# Openbook_Schematics.net
KiCad netlist of a schematic drawn in EAGLE
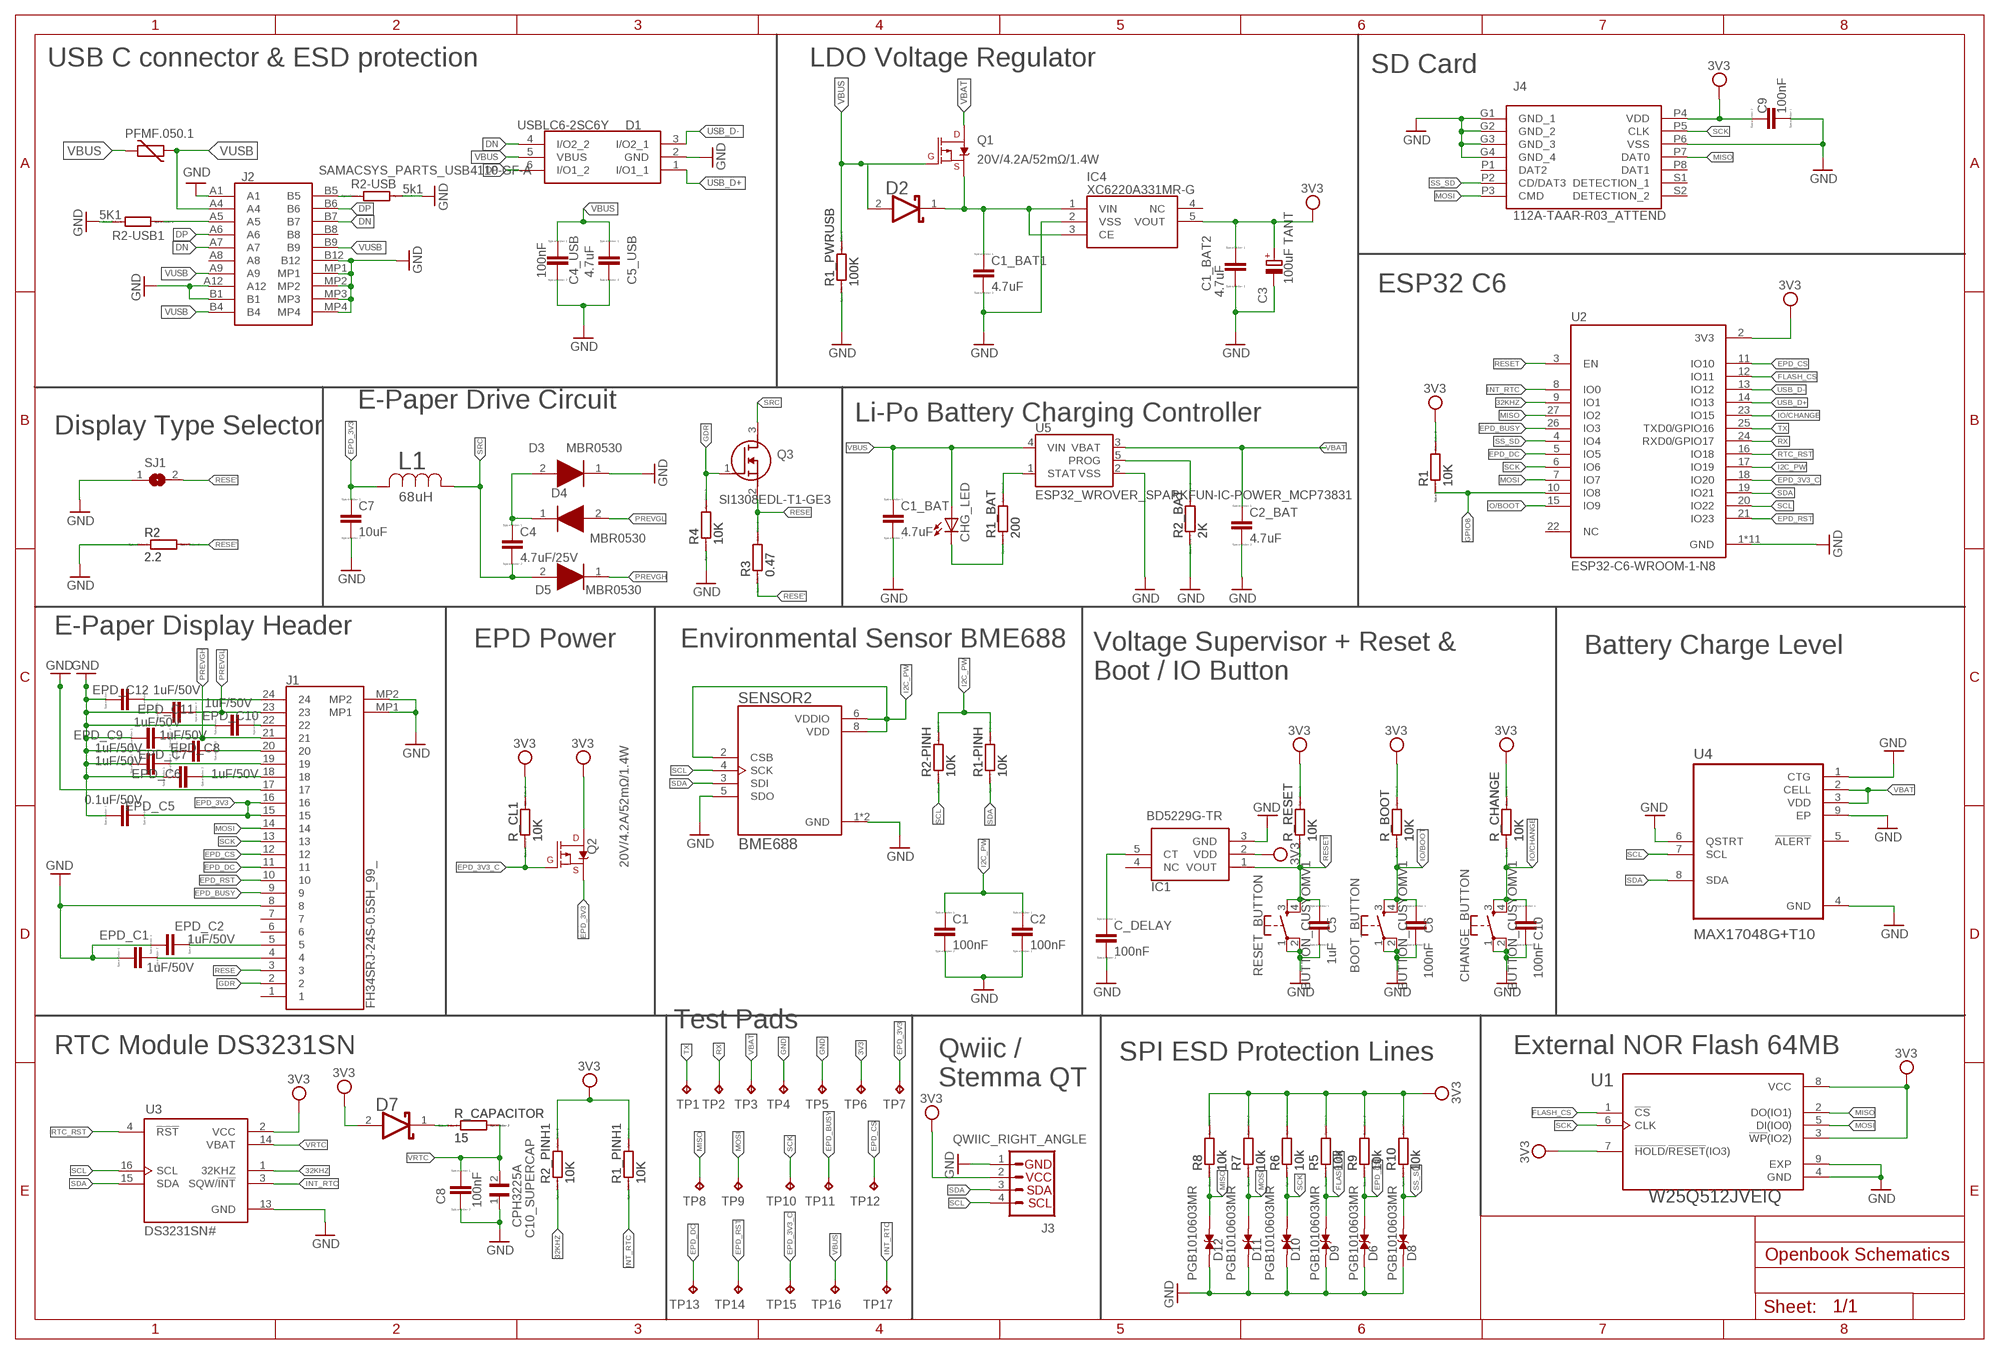
[diagram p0: schematic, sheet 1]

(export (version "E")
  (design (tool "Eeschema 10.0.6"))
  (components
    (comp (ref "BOOT_BUTTON")
      (value "BUTTON_CUSYOMV1")
      (footprint "eagle-import:MYBUTTON")
      (libsource (lib "eagle-import") (part "BUTTON_CUSYOMV1"))
    )
    (comp (ref "C1")
      (value "100nF")
      (footprint "eagle-import:EAGLE-LTSPICE_C0402")
      (libsource (lib "eagle-import") (part "EAGLE-LTSPICE_CC0402"))
    )
    (comp (ref "C1_BAT")
      (value "4.7uF")
      (footprint "eagle-import:EAGLE-LTSPICE_C0402")
      (libsource (lib "eagle-import") (part "EAGLE-LTSPICE_CC0402"))
    )
    (comp (ref "C1_BAT1")
      (value "4.7uF")
      (footprint "eagle-import:ESP32_WROVER_EAGLE-LTSPICE_C0402")
      (libsource (lib "eagle-import") (part "ESP32_WROVER_EAGLE-LTSPICE_CC0402"))
    )
    (comp (ref "C1_BAT2")
      (value "4.7uF")
      (footprint "eagle-import:EAGLE-LTSPICE_C0402")
      (libsource (lib "eagle-import") (part "EAGLE-LTSPICE_CC0402"))
    )
    (comp (ref "C2")
      (value "100nF")
      (footprint "eagle-import:EAGLE-LTSPICE_C0402")
      (libsource (lib "eagle-import") (part "EAGLE-LTSPICE_CC0402"))
    )
    (comp (ref "C2_BAT")
      (value "4.7uF")
      (footprint "eagle-import:EAGLE-LTSPICE_C0402")
      (libsource (lib "eagle-import") (part "EAGLE-LTSPICE_CC0402"))
    )
    (comp (ref "C3")
      (value "100uF TANT")
      (footprint "eagle-import:RCL_CT3528")
      (libsource (lib "eagle-import") (part "RCL_CPOL-EUCT3528"))
    )
    (comp (ref "C4")
      (value "4.7uF/25V")
      (footprint "eagle-import:EAGLE-LTSPICE_C0402")
      (libsource (lib "eagle-import") (part "EAGLE-LTSPICE_CC0402"))
    )
    (comp (ref "C4_USB")
      (value "100nF")
      (footprint "eagle-import:EAGLE-LTSPICE_C0402")
      (libsource (lib "eagle-import") (part "EAGLE-LTSPICE_CC0402"))
    )
    (comp (ref "C5")
      (value "1uF")
      (footprint "eagle-import:EAGLE-LTSPICE_C0402")
      (libsource (lib "eagle-import") (part "EAGLE-LTSPICE_CC0402"))
    )
    (comp (ref "C5_USB")
      (value "4.7uF")
      (footprint "eagle-import:EAGLE-LTSPICE_C0402")
      (libsource (lib "eagle-import") (part "EAGLE-LTSPICE_CC0402"))
    )
    (comp (ref "C6")
      (value "100nF")
      (footprint "eagle-import:EAGLE-LTSPICE_C0402")
      (libsource (lib "eagle-import") (part "EAGLE-LTSPICE_CC0402"))
    )
    (comp (ref "C7")
      (value "10uF")
      (footprint "eagle-import:EAGLE-LTSPICE_C0402")
      (libsource (lib "eagle-import") (part "EAGLE-LTSPICE_CC0402"))
    )
    (comp (ref "C8")
      (value "100nF")
      (footprint "eagle-import:EAGLE-LTSPICE_C0402")
      (libsource (lib "eagle-import") (part "EAGLE-LTSPICE_CC0402"))
    )
    (comp (ref "C9")
      (value "100nF")
      (footprint "eagle-import:EAGLE-LTSPICE_C0402")
      (libsource (lib "eagle-import") (part "EAGLE-LTSPICE_CC0402"))
    )
    (comp (ref "C10")
      (value "100nF")
      (footprint "eagle-import:EAGLE-LTSPICE_C0402")
      (libsource (lib "eagle-import") (part "EAGLE-LTSPICE_CC0402"))
    )
    (comp (ref "C10_SUPERCAP")
      (value "CPH3225A")
      (footprint "eagle-import:CAPCP3225X100N")
      (fields (field (name "MF") "Seiko Instruments"))
      (libsource (lib "eagle-import") (part "CPH3225A"))
    )
    (comp (ref "CHANGE_BUTTON")
      (value "BUTTON_CUSYOMV1")
      (footprint "eagle-import:MYBUTTON")
      (libsource (lib "eagle-import") (part "BUTTON_CUSYOMV1"))
    )
    (comp (ref "CHG_LED")
      (value "ADAFRUIT_LEDCHIP-LED0603")
      (footprint "eagle-import:ADAFRUIT_CHIP-LED0603")
      (libsource (lib "eagle-import") (part "ADAFRUIT_LEDCHIP-LED0603"))
    )
    (comp (ref "C_DELAY")
      (value "100nF")
      (footprint "eagle-import:EAGLE-LTSPICE_C0402")
      (libsource (lib "eagle-import") (part "EAGLE-LTSPICE_CC0402"))
    )
    (comp (ref "D1")
      (value "USBLC6-2SC6Y")
      (footprint "eagle-import:SOT95P280X145-6N")
      (fields (field (name "MF") "STMicroelectronics"))
      (libsource (lib "eagle-import") (part "USBLC6-2SC6Y"))
    )
    (comp (ref "D2")
      (value "ESP32_WROVER_AVX---SD0805S020S1R0_AVX_SD0805S020S1R0_0_0AVX_SD0805S020S1R0_0_0")
      (footprint "eagle-import:ESP32_WROVER_AVX---SD0805S020S1R0_AVX_SD0805S020S1R0_0")
      (fields
        (field (name "DIGIKEY_PART_NUMBER") "478-7800-1-ND")
        (field (name "MF") "AVX")
        (field (name "MOUSER_PART_NUMBER") "581-SD0805S020S1R0")
      )
      (libsource (lib "eagle-import") (part "ESP32_WROVER_AVX---SD0805S020S1R0_AVX_SD0805S020S1R0_0_0AVX_SD0805S020S1R0_0_0"))
    )
    (comp (ref "D3")
      (value "MBR0530")
      (footprint "eagle-import:SOD3716X135N")
      (fields (field (name "MF") "ON Semiconductor"))
      (libsource (lib "eagle-import") (part "MBR0530"))
    )
    (comp (ref "D4")
      (value "MBR0530")
      (footprint "eagle-import:SOD3716X135N")
      (fields (field (name "MF") "ON Semiconductor"))
      (libsource (lib "eagle-import") (part "MBR0530"))
    )
    (comp (ref "D5")
      (value "MBR0530")
      (footprint "eagle-import:SOD3716X135N")
      (fields (field (name "MF") "ON Semiconductor"))
      (libsource (lib "eagle-import") (part "MBR0530"))
    )
    (comp (ref "D6")
      (value "PGB1010603MR")
      (footprint "eagle-import:DIOC1608X36N")
      (fields (field (name "MF") "Littelfuse Inc."))
      (libsource (lib "eagle-import") (part "PGB1010603MR"))
    )
    (comp (ref "D7")
      (value "ESP32_WROVER_AVX---SD0805S020S1R0_AVX_SD0805S020S1R0_0_0AVX_SD0805S020S1R0_0_0")
      (footprint "eagle-import:ESP32_WROVER_AVX---SD0805S020S1R0_AVX_SD0805S020S1R0_0")
      (fields
        (field (name "DIGIKEY_PART_NUMBER") "478-7800-1-ND")
        (field (name "MF") "AVX")
        (field (name "MOUSER_PART_NUMBER") "581-SD0805S020S1R0")
      )
      (libsource (lib "eagle-import") (part "ESP32_WROVER_AVX---SD0805S020S1R0_AVX_SD0805S020S1R0_0_0AVX_SD0805S020S1R0_0_0"))
    )
    (comp (ref "D8")
      (value "PGB1010603MR")
      (footprint "eagle-import:DIOC1608X36N")
      (fields (field (name "MF") "Littelfuse Inc."))
      (libsource (lib "eagle-import") (part "PGB1010603MR"))
    )
    (comp (ref "D9")
      (value "PGB1010603MR")
      (footprint "eagle-import:DIOC1608X36N")
      (fields (field (name "MF") "Littelfuse Inc."))
      (libsource (lib "eagle-import") (part "PGB1010603MR"))
    )
    (comp (ref "D10")
      (value "PGB1010603MR")
      (footprint "eagle-import:DIOC1608X36N")
      (fields (field (name "MF") "Littelfuse Inc."))
      (libsource (lib "eagle-import") (part "PGB1010603MR"))
    )
    (comp (ref "D11")
      (value "PGB1010603MR")
      (footprint "eagle-import:DIOC1608X36N")
      (fields (field (name "MF") "Littelfuse Inc."))
      (libsource (lib "eagle-import") (part "PGB1010603MR"))
    )
    (comp (ref "D12")
      (value "PGB1010603MR")
      (footprint "eagle-import:DIOC1608X36N")
      (fields (field (name "MF") "Littelfuse Inc."))
      (libsource (lib "eagle-import") (part "PGB1010603MR"))
    )
    (comp (ref "EPD_C1")
      (value "1uF/50V")
      (footprint "eagle-import:EAGLE-LTSPICE_C0402")
      (libsource (lib "eagle-import") (part "EAGLE-LTSPICE_CC0402"))
    )
    (comp (ref "EPD_C2")
      (value "1uF/50V")
      (footprint "eagle-import:EAGLE-LTSPICE_C0402")
      (libsource (lib "eagle-import") (part "EAGLE-LTSPICE_CC0402"))
    )
    (comp (ref "EPD_C5")
      (value "0.1uF/50V")
      (footprint "eagle-import:EAGLE-LTSPICE_C0402")
      (libsource (lib "eagle-import") (part "EAGLE-LTSPICE_CC0402"))
    )
    (comp (ref "EPD_C6")
      (value "1uF/50V")
      (footprint "eagle-import:EAGLE-LTSPICE_C0402")
      (libsource (lib "eagle-import") (part "EAGLE-LTSPICE_CC0402"))
    )
    (comp (ref "EPD_C7")
      (value "1uF/50V")
      (footprint "eagle-import:EAGLE-LTSPICE_C0402")
      (libsource (lib "eagle-import") (part "EAGLE-LTSPICE_CC0402"))
    )
    (comp (ref "EPD_C8")
      (value "1uF/50V")
      (footprint "eagle-import:EAGLE-LTSPICE_C0402")
      (libsource (lib "eagle-import") (part "EAGLE-LTSPICE_CC0402"))
    )
    (comp (ref "EPD_C9")
      (value "1uF/50V")
      (footprint "eagle-import:EAGLE-LTSPICE_C0402")
      (libsource (lib "eagle-import") (part "EAGLE-LTSPICE_CC0402"))
    )
    (comp (ref "EPD_C10")
      (value "1uF/50V")
      (footprint "eagle-import:EAGLE-LTSPICE_C0402")
      (libsource (lib "eagle-import") (part "EAGLE-LTSPICE_CC0402"))
    )
    (comp (ref "EPD_C11")
      (value "1uF/50V")
      (footprint "eagle-import:EAGLE-LTSPICE_C0402")
      (libsource (lib "eagle-import") (part "EAGLE-LTSPICE_CC0402"))
    )
    (comp (ref "EPD_C12")
      (value "1uF/50V")
      (footprint "eagle-import:EAGLE-LTSPICE_C0402")
      (libsource (lib "eagle-import") (part "EAGLE-LTSPICE_CC0402"))
    )
    (comp (ref "IC1")
      (value "BD5229G-TR")
      (footprint "eagle-import:SOT95P280X125-5N")
      (fields (field (name "MOUSER_PART_NUMBER") "755-BD5229G-TR"))
      (libsource (lib "eagle-import") (part "BD5229G-TR"))
    )
    (comp (ref "IC4")
      (value "XC6220A331MR-G")
      (footprint "eagle-import:SOT95P280X120-5N")
      (fields (field (name "MOUSER_PART_NUMBER") "865-XC6220A331MR-G"))
      (libsource (lib "eagle-import") (part "XC6220A331MR-G"))
    )
    (comp (ref "J1")
      (value "FH34SRJ-24S-0.5SH_99_")
      (footprint "eagle-import:FH34SRJ24S05SH99")
      (fields
        (field (name "MANUFACTURER_PART_NUMBER") "FH34SRJ-24S-0.5SH(99)")
        (field (name "MOUSER_PART_NUMBER") "798-FH34SRJ24S05SH99")
      )
      (libsource (lib "eagle-import") (part "FH34SRJ-24S-0.5SH_99_"))
    )
    (comp (ref "J2")
      (value "SAMACSYS_PARTS_USB4110-GF-A")
      (footprint "eagle-import:SAMACSYS_PARTS_USB4110GFA")
      (fields
        (field (name "MANUFACTURER_PART_NUMBER") "USB4110-GF-A")
        (field (name "MOUSER_PART_NUMBER") "640-USB4110-GF-A")
      )
      (libsource (lib "eagle-import") (part "SAMACSYS_PARTS_USB4110-GF-A"))
    )
    (comp (ref "J3")
      (value "QWIIC_RIGHT_ANGLE")
      (footprint "eagle-import:JST04_1MM_RA")
      (libsource (lib "eagle-import") (part "QWIIC_CONNECTORJS-1MM"))
    )
    (comp (ref "J4")
      (value "112A-TAAR-R03_ATTEND")
      (footprint "eagle-import:112ATAARR03ATTEND")
      (fields (field (name "MANUFACTURER_PART_NUMBER") "112A-TAAR-R03 ATTEND"))
      (libsource (lib "eagle-import") (part "112A-TAAR-R03_ATTEND"))
    )
    (comp (ref "L1")
      (value "68uH")
      (footprint "eagle-import:IND_4828-WE-TPC_WRE")
      (fields
        (field (name "MANUFACTURER_PART_NUMBER") "744043680")
        (field (name "COPYRIGHT") "Copyright (C) 2024 Ultra Librarian. All rights reserved.")
      )
      (libsource (lib "eagle-import") (part "744043680IND_4828-WE-TPC_WRE"))
    )
    (comp (ref "PFMF.050.1")
      (value "ESP32C6_VARISTORCN1812")
      (footprint "eagle-import:ESP32C6_VARISTOR_CT_CN1812")
      (libsource (lib "eagle-import") (part "ESP32C6_VARISTORCN1812"))
    )
    (comp (ref "Q1")
      (value "20V/4.2A/52mΩ/1.4W")
      (footprint "eagle-import:ESP32_WROVER_SPARKFUN-DISCRETESEMI_SOT23-3")
      (libsource (lib "eagle-import") (part "ESP32_WROVER_SPARKFUN-DISCRETESEMI_MOSFET_PCH-DMG2305UX-7"))
    )
    (comp (ref "Q2")
      (value "20V/4.2A/52mΩ/1.4W")
      (footprint "eagle-import:ESP32_WROVER_SPARKFUN-DISCRETESEMI_SOT23-3")
      (libsource (lib "eagle-import") (part "ESP32_WROVER_SPARKFUN-DISCRETESEMI_MOSFET_PCH-DMG2305UX-7"))
    )
    (comp (ref "Q3")
      (value "SI1308EDL-T1-GE3")
      (footprint "eagle-import:SOT65P210X110-3N")
      (fields (field (name "MF") "Vishay Siliconix"))
      (libsource (lib "eagle-import") (part "SI1308EDL-T1-GE3"))
    )
    (comp (ref "R1")
      (value "10K")
      (footprint "eagle-import:ESP32_WROVER_EAGLE-LTSPICE_R0402")
      (libsource (lib "eagle-import") (part "ESP32_WROVER_EAGLE-LTSPICE_RR0402"))
    )
    (comp (ref "R1-PINH")
      (value "10K")
      (footprint "eagle-import:ESP32_WROVER_EAGLE-LTSPICE_R0402")
      (libsource (lib "eagle-import") (part "ESP32_WROVER_EAGLE-LTSPICE_RR0402"))
    )
    (comp (ref "R1_BAT")
      (value "200")
      (footprint "eagle-import:ESP32_WROVER_EAGLE-LTSPICE_R0402")
      (libsource (lib "eagle-import") (part "ESP32_WROVER_EAGLE-LTSPICE_RR0402"))
    )
    (comp (ref "R1_PINH1")
      (value "10K")
      (footprint "eagle-import:ESP32_WROVER_EAGLE-LTSPICE_R0402")
      (libsource (lib "eagle-import") (part "ESP32_WROVER_EAGLE-LTSPICE_RR0402"))
    )
    (comp (ref "R1_PWRUSB")
      (value "100K")
      (footprint "eagle-import:ESP32_WROVER_EAGLE-LTSPICE_R0402")
      (libsource (lib "eagle-import") (part "ESP32_WROVER_EAGLE-LTSPICE_RR0402"))
    )
    (comp (ref "R2")
      (value "2.2")
      (footprint "eagle-import:ESP32_WROVER_EAGLE-LTSPICE_R0402")
      (libsource (lib "eagle-import") (part "ESP32_WROVER_EAGLE-LTSPICE_RR0402"))
    )
    (comp (ref "R2-PINH")
      (value "10K")
      (footprint "eagle-import:ESP32_WROVER_EAGLE-LTSPICE_R0402")
      (libsource (lib "eagle-import") (part "ESP32_WROVER_EAGLE-LTSPICE_RR0402"))
    )
    (comp (ref "R2-USB")
      (value "5k1")
      (footprint "eagle-import:ESP32_WROVER_EAGLE-LTSPICE_R0402")
      (libsource (lib "eagle-import") (part "ESP32_WROVER_EAGLE-LTSPICE_RR0402"))
    )
    (comp (ref "R2-USB1")
      (value "5K1")
      (footprint "eagle-import:ESP32_WROVER_EAGLE-LTSPICE_R0402")
      (libsource (lib "eagle-import") (part "ESP32_WROVER_EAGLE-LTSPICE_RR0402"))
    )
    (comp (ref "R2_BAT")
      (value "2K")
      (footprint "eagle-import:ESP32_WROVER_EAGLE-LTSPICE_R0402")
      (libsource (lib "eagle-import") (part "ESP32_WROVER_EAGLE-LTSPICE_RR0402"))
    )
    (comp (ref "R2_PINH1")
      (value "10K")
      (footprint "eagle-import:ESP32_WROVER_EAGLE-LTSPICE_R0402")
      (libsource (lib "eagle-import") (part "ESP32_WROVER_EAGLE-LTSPICE_RR0402"))
    )
    (comp (ref "R3")
      (value "0.47")
      (footprint "eagle-import:ESP32_WROVER_EAGLE-LTSPICE_R0402")
      (libsource (lib "eagle-import") (part "ESP32_WROVER_EAGLE-LTSPICE_RR0402"))
    )
    (comp (ref "R4")
      (value "10K")
      (footprint "eagle-import:ESP32_WROVER_EAGLE-LTSPICE_R0402")
      (libsource (lib "eagle-import") (part "ESP32_WROVER_EAGLE-LTSPICE_RR0402"))
    )
    (comp (ref "R5")
      (value "10k")
      (footprint "eagle-import:ESP32_WROVER_EAGLE-LTSPICE_R0402")
      (libsource (lib "eagle-import") (part "ESP32_WROVER_EAGLE-LTSPICE_RR0402"))
    )
    (comp (ref "R6")
      (value "10k")
      (footprint "eagle-import:ESP32_WROVER_EAGLE-LTSPICE_R0402")
      (libsource (lib "eagle-import") (part "ESP32_WROVER_EAGLE-LTSPICE_RR0402"))
    )
    (comp (ref "R7")
      (value "10k")
      (footprint "eagle-import:ESP32_WROVER_EAGLE-LTSPICE_R0402")
      (libsource (lib "eagle-import") (part "ESP32_WROVER_EAGLE-LTSPICE_RR0402"))
    )
    (comp (ref "R8")
      (value "10k")
      (footprint "eagle-import:ESP32_WROVER_EAGLE-LTSPICE_R0402")
      (libsource (lib "eagle-import") (part "ESP32_WROVER_EAGLE-LTSPICE_RR0402"))
    )
    (comp (ref "R9")
      (value "10k")
      (footprint "eagle-import:ESP32_WROVER_EAGLE-LTSPICE_R0402")
      (libsource (lib "eagle-import") (part "ESP32_WROVER_EAGLE-LTSPICE_RR0402"))
    )
    (comp (ref "R10")
      (value "10k")
      (footprint "eagle-import:ESP32_WROVER_EAGLE-LTSPICE_R0402")
      (libsource (lib "eagle-import") (part "ESP32_WROVER_EAGLE-LTSPICE_RR0402"))
    )
    (comp (ref "RESET_BUTTON")
      (value "BUTTON_CUSYOMV1")
      (footprint "eagle-import:MYBUTTON")
      (libsource (lib "eagle-import") (part "BUTTON_CUSYOMV1"))
    )
    (comp (ref "R_BOOT")
      (value "10K")
      (footprint "eagle-import:ESP32_WROVER_EAGLE-LTSPICE_R0402")
      (libsource (lib "eagle-import") (part "ESP32_WROVER_EAGLE-LTSPICE_RR0402"))
    )
    (comp (ref "R_CAPACITOR")
      (value "15")
      (footprint "eagle-import:ESP32_WROVER_EAGLE-LTSPICE_R0402")
      (libsource (lib "eagle-import") (part "ESP32_WROVER_EAGLE-LTSPICE_RR0402"))
    )
    (comp (ref "R_CHANGE")
      (value "10K")
      (footprint "eagle-import:ESP32_WROVER_EAGLE-LTSPICE_R0402")
      (libsource (lib "eagle-import") (part "ESP32_WROVER_EAGLE-LTSPICE_RR0402"))
    )
    (comp (ref "R_CL1")
      (value "10K")
      (footprint "eagle-import:ESP32_WROVER_EAGLE-LTSPICE_R0402")
      (libsource (lib "eagle-import") (part "ESP32_WROVER_EAGLE-LTSPICE_RR0402"))
    )
    (comp (ref "R_RESET")
      (value "10K")
      (footprint "eagle-import:ESP32_WROVER_EAGLE-LTSPICE_R0402")
      (libsource (lib "eagle-import") (part "ESP32_WROVER_EAGLE-LTSPICE_RR0402"))
    )
    (comp (ref "SENSOR2")
      (value "BME688")
      (footprint "eagle-import:ESP32_WROVER_BME680_PSON80P300X300X100-8N")
      (fields (field (name "MF") "Bosch Sensortec") (field (name "MP") "BME680"))
      (libsource (lib "eagle-import") (part "ESP32_WROVER_BME680_BME680"))
    )
    (comp (ref "SJ1") (value "SJ") (footprint "eagle-import:SJ") (libsource (lib "eagle-import") (part "SJ")))
    (comp (ref "TP1")
      (value "TPTP20R")
      (footprint "eagle-import:TP20R")
      (libsource (lib "eagle-import") (part "TPTP20R"))
    )
    (comp (ref "TP2")
      (value "TPTP20R")
      (footprint "eagle-import:TP20R")
      (libsource (lib "eagle-import") (part "TPTP20R"))
    )
    (comp (ref "TP3")
      (value "TPTP20R")
      (footprint "eagle-import:TP20R")
      (libsource (lib "eagle-import") (part "TPTP20R"))
    )
    (comp (ref "TP4")
      (value "TPTP20R")
      (footprint "eagle-import:TP20R")
      (libsource (lib "eagle-import") (part "TPTP20R"))
    )
    (comp (ref "TP5")
      (value "TPTP20R")
      (footprint "eagle-import:TP20R")
      (libsource (lib "eagle-import") (part "TPTP20R"))
    )
    (comp (ref "TP6")
      (value "TPTP20R")
      (footprint "eagle-import:TP20R")
      (libsource (lib "eagle-import") (part "TPTP20R"))
    )
    (comp (ref "TP7")
      (value "TPTP20R")
      (footprint "eagle-import:TP20R")
      (libsource (lib "eagle-import") (part "TPTP20R"))
    )
    (comp (ref "TP8")
      (value "TPTP20R")
      (footprint "eagle-import:TP20R")
      (libsource (lib "eagle-import") (part "TPTP20R"))
    )
    (comp (ref "TP9")
      (value "TPTP20R")
      (footprint "eagle-import:TP20R")
      (libsource (lib "eagle-import") (part "TPTP20R"))
    )
    (comp (ref "TP10")
      (value "TPTP20R")
      (footprint "eagle-import:TP20R")
      (libsource (lib "eagle-import") (part "TPTP20R"))
    )
    (comp (ref "TP11")
      (value "TPTP20R")
      (footprint "eagle-import:TP20R")
      (libsource (lib "eagle-import") (part "TPTP20R"))
    )
    (comp (ref "TP12")
      (value "TPTP20R")
      (footprint "eagle-import:TP20R")
      (libsource (lib "eagle-import") (part "TPTP20R"))
    )
    (comp (ref "TP13")
      (value "TPTP20R")
      (footprint "eagle-import:TP20R")
      (libsource (lib "eagle-import") (part "TPTP20R"))
    )
    (comp (ref "TP14")
      (value "TPTP20R")
      (footprint "eagle-import:TP20R")
      (libsource (lib "eagle-import") (part "TPTP20R"))
    )
    (comp (ref "TP15")
      (value "TPTP20R")
      (footprint "eagle-import:TP20R")
      (libsource (lib "eagle-import") (part "TPTP20R"))
    )
    (comp (ref "TP16")
      (value "TPTP20R")
      (footprint "eagle-import:TP20R")
      (libsource (lib "eagle-import") (part "TPTP20R"))
    )
    (comp (ref "TP17")
      (value "TPTP20R")
      (footprint "eagle-import:TP20R")
      (libsource (lib "eagle-import") (part "TPTP20R"))
    )
    (comp (ref "U1")
      (value "W25Q512JVEIQ")
      (footprint "eagle-import:SON127P600X800X80-9N")
      (fields (field (name "MF") "Winbond Electronics"))
      (libsource (lib "eagle-import") (part "W25Q512JVEIQ"))
    )
    (comp (ref "U2")
      (value "ESP32-C6-WROOM-1-N8")
      (footprint "eagle-import:XCVR_ESP32-C6-WROOM-1-N8")
      (fields (field (name "MF") "Espressif Systems"))
      (libsource (lib "eagle-import") (part "ESP32-C6-WROOM-1-N8"))
    )
    (comp (ref "U3")
      (value "DS3231SN#")
      (footprint "eagle-import:SOIC127P1032X265-16N")
      (fields (field (name "MF") "Analog Devices"))
      (libsource (lib "eagle-import") (part "DS3231SN#"))
    )
    (comp (ref "U4")
      (value "MAX17048G+T10")
      (footprint "eagle-import:SON50P200X200X80-9N")
      (fields (field (name "MF") "Analog Devices"))
      (libsource (lib "eagle-import") (part "MAX17048G+T10"))
    )
    (comp (ref "U5")
      (value "ESP32_WROVER_SPARKFUN-IC-POWER_MCP73831")
      (footprint "eagle-import:ESP32_WROVER_SPARKFUN-IC-POWER_SOT23-5")
      (libsource (lib "eagle-import") (part "ESP32_WROVER_SPARKFUN-IC-POWER_MCP73831"))
    )
  )
  (nets
    (net (code "1") (name "3V3") (class "Default")
      (node (ref "C1_BAT2") (pin "1") (pinfunction "1_1") (pintype "passive"))
      (node (ref "C3") (pin "+") (pinfunction "+_+") (pintype "passive"))
      (node (ref "C9") (pin "2") (pinfunction "2_2") (pintype "passive"))
      (node (ref "D7") (pin "2") (pinfunction "ANODE_2") (pintype "bidirectional"))
      (node (ref "IC1") (pin "2") (pinfunction "VDD_2") (pintype "bidirectional"))
      (node (ref "IC4") (pin "5") (pinfunction "VOUT_5") (pintype "bidirectional"))
      (node (ref "J3") (pin "2") (pinfunction "2_2") (pintype "power_in"))
      (node (ref "J4") (pin "P4") (pinfunction "VDD_P4") (pintype "bidirectional"))
      (node (ref "Q2") (pin "3") (pinfunction "D_3") (pintype "bidirectional"))
      (node (ref "R1") (pin "2") (pinfunction "2_2") (pintype "passive"))
      (node (ref "R10") (pin "2") (pinfunction "2_2") (pintype "passive"))
      (node (ref "R1_PINH1") (pin "2") (pinfunction "2_2") (pintype "passive"))
      (node (ref "R2_PINH1") (pin "2") (pinfunction "2_2") (pintype "passive"))
      (node (ref "R5") (pin "2") (pinfunction "2_2") (pintype "passive"))
      (node (ref "R6") (pin "2") (pinfunction "2_2") (pintype "passive"))
      (node (ref "R7") (pin "2") (pinfunction "2_2") (pintype "passive"))
      (node (ref "R8") (pin "2") (pinfunction "2_2") (pintype "passive"))
      (node (ref "R9") (pin "2") (pinfunction "2_2") (pintype "passive"))
      (node (ref "R_BOOT") (pin "2") (pinfunction "2_2") (pintype "passive"))
      (node (ref "R_CHANGE") (pin "2") (pinfunction "2_2") (pintype "passive"))
      (node (ref "R_CL1") (pin "2") (pinfunction "2_2") (pintype "passive"))
      (node (ref "R_RESET") (pin "2") (pinfunction "2_2") (pintype "passive"))
      (node (ref "TP6") (pin "TP") (pinfunction "TP_TP") (pintype "input"))
      (node (ref "U1") (pin "3") (pinfunction "~{WP}(IO2)_3") (pintype "bidirectional"))
      (node (ref "U1") (pin "7") (pinfunction "~{HOLD}/~{RESET}(IO3)_7") (pintype "bidirectional"))
      (node (ref "U1") (pin "8") (pinfunction "VCC_8") (pintype "power_in"))
      (node (ref "U2") (pin "2") (pinfunction "3V3_2") (pintype "power_in"))
      (node (ref "U3") (pin "2") (pinfunction "VCC_2") (pintype "power_in"))
    )
    (net (code "2") (name "32KHZ") (class "Default")
      (node (ref "R2_PINH1") (pin "1") (pinfunction "1_1") (pintype "passive"))
      (node (ref "U2") (pin "9") (pinfunction "IO1_9") (pintype "bidirectional"))
      (node (ref "U3") (pin "1") (pinfunction "32KHZ_1") (pintype "output"))
    )
    (net (code "3") (name "DN") (class "Default")
      (node (ref "D1") (pin "4") (pinfunction "I/O2_2_4") (pintype "bidirectional"))
      (node (ref "J2") (pin "A7") (pinfunction "A7_A7") (pintype "bidirectional"))
      (node (ref "J2") (pin "B7") (pinfunction "B7_B7") (pintype "bidirectional"))
    )
    (net (code "4") (name "DP") (class "Default")
      (node (ref "D1") (pin "6") (pinfunction "I/O1_2_6") (pintype "bidirectional"))
      (node (ref "J2") (pin "A6") (pinfunction "A6_A6") (pintype "bidirectional"))
      (node (ref "J2") (pin "B6") (pinfunction "B6_B6") (pintype "bidirectional"))
    )
    (net (code "5") (name "EPD_3V3") (class "Default")
      (node (ref "C7") (pin "1") (pinfunction "1_1") (pintype "passive"))
      (node (ref "EPD_C5") (pin "2") (pinfunction "2_2") (pintype "passive"))
      (node (ref "J1") (pin "15") (pinfunction "15_15") (pintype "bidirectional"))
      (node (ref "J1") (pin "16") (pinfunction "16_16") (pintype "bidirectional"))
      (node (ref "L1") (pin "2") (pinfunction "2_2") (pintype "passive"))
      (node (ref "Q2") (pin "2") (pinfunction "S_2") (pintype "bidirectional"))
      (node (ref "TP7") (pin "TP") (pinfunction "TP_TP") (pintype "input"))
    )
    (net (code "6") (name "EPD_3V3_C") (class "Default")
      (node (ref "Q2") (pin "1") (pinfunction "G_1") (pintype "bidirectional"))
      (node (ref "R_CL1") (pin "1") (pinfunction "1_1") (pintype "passive"))
      (node (ref "TP15") (pin "TP") (pinfunction "TP_TP") (pintype "input"))
      (node (ref "U2") (pin "18") (pinfunction "IO20_18") (pintype "bidirectional"))
    )
    (net (code "7") (name "EPD_BUSY") (class "Default")
      (node (ref "J1") (pin "9") (pinfunction "9_9") (pintype "bidirectional"))
      (node (ref "TP11") (pin "TP") (pinfunction "TP_TP") (pintype "input"))
      (node (ref "U2") (pin "26") (pinfunction "IO3_26") (pintype "bidirectional"))
    )
    (net (code "8") (name "EPD_CS") (class "Default")
      (node (ref "D6") (pin "2") (pinfunction "2_2") (pintype "passive"))
      (node (ref "J1") (pin "12") (pinfunction "12_12") (pintype "bidirectional"))
      (node (ref "R9") (pin "1") (pinfunction "1_1") (pintype "passive"))
      (node (ref "TP12") (pin "TP") (pinfunction "TP_TP") (pintype "input"))
      (node (ref "U2") (pin "11") (pinfunction "IO10_11") (pintype "bidirectional"))
    )
    (net (code "9") (name "EPD_DC") (class "Default")
      (node (ref "J1") (pin "11") (pinfunction "11_11") (pintype "bidirectional"))
      (node (ref "TP13") (pin "TP") (pinfunction "TP_TP") (pintype "input"))
      (node (ref "U2") (pin "5") (pinfunction "IO5_5") (pintype "bidirectional"))
    )
    (net (code "10") (name "EPD_RST") (class "Default")
      (node (ref "J1") (pin "10") (pinfunction "10_10") (pintype "bidirectional"))
      (node (ref "TP14") (pin "TP") (pinfunction "TP_TP") (pintype "input"))
      (node (ref "U2") (pin "21") (pinfunction "IO23_21") (pintype "bidirectional"))
    )
    (net (code "11") (name "FLASH_CS") (class "Default")
      (node (ref "D9") (pin "2") (pinfunction "2_2") (pintype "passive"))
      (node (ref "R5") (pin "1") (pinfunction "1_1") (pintype "passive"))
      (node (ref "U1") (pin "1") (pinfunction "~{CS}_1") (pintype "input"))
      (node (ref "U2") (pin "12") (pinfunction "IO11_12") (pintype "bidirectional"))
    )
    (net (code "12") (name "GDR") (class "Default")
      (node (ref "J1") (pin "2") (pinfunction "2_2") (pintype "bidirectional"))
      (node (ref "Q3") (pin "1") (pinfunction "G_1") (pintype "bidirectional"))
      (node (ref "R4") (pin "2") (pinfunction "2_2") (pintype "passive"))
    )
    (net (code "13") (name "GND") (class "Default")
      (node (ref "BOOT_BUTTON") (pin "1") (pinfunction "1_1") (pintype "passive"))
      (node (ref "BOOT_BUTTON") (pin "2") (pinfunction "2_2") (pintype "passive"))
      (node (ref "C1") (pin "2") (pinfunction "2_2") (pintype "passive"))
      (node (ref "C10") (pin "2") (pinfunction "2_2") (pintype "passive"))
      (node (ref "C10_SUPERCAP") (pin "1") (pinfunction "1_1") (pintype "passive"))
      (node (ref "C1_BAT") (pin "2") (pinfunction "2_2") (pintype "passive"))
      (node (ref "C1_BAT1") (pin "2") (pinfunction "2_2") (pintype "passive"))
      (node (ref "C1_BAT2") (pin "2") (pinfunction "2_2") (pintype "passive"))
      (node (ref "C2") (pin "2") (pinfunction "2_2") (pintype "passive"))
      (node (ref "C2_BAT") (pin "2") (pinfunction "2_2") (pintype "passive"))
      (node (ref "C3") (pin "-") (pinfunction "-_-") (pintype "passive"))
      (node (ref "C4_USB") (pin "2") (pinfunction "2_2") (pintype "passive"))
      (node (ref "C5") (pin "2") (pinfunction "2_2") (pintype "passive"))
      (node (ref "C5_USB") (pin "2") (pinfunction "2_2") (pintype "passive"))
      (node (ref "C6") (pin "2") (pinfunction "2_2") (pintype "passive"))
      (node (ref "C7") (pin "2") (pinfunction "2_2") (pintype "passive"))
      (node (ref "C8") (pin "2") (pinfunction "2_2") (pintype "passive"))
      (node (ref "C9") (pin "1") (pinfunction "1_1") (pintype "passive"))
      (node (ref "CHANGE_BUTTON") (pin "1") (pinfunction "1_1") (pintype "passive"))
      (node (ref "CHANGE_BUTTON") (pin "2") (pinfunction "2_2") (pintype "passive"))
      (node (ref "C_DELAY") (pin "2") (pinfunction "2_2") (pintype "passive"))
      (node (ref "D1") (pin "2") (pinfunction "GND_2") (pintype "bidirectional"))
      (node (ref "D10") (pin "1") (pinfunction "1_1") (pintype "passive"))
      (node (ref "D11") (pin "1") (pinfunction "1_1") (pintype "passive"))
      (node (ref "D12") (pin "1") (pinfunction "1_1") (pintype "passive"))
      (node (ref "D3") (pin "1") (pinfunction "K_1") (pintype "bidirectional"))
      (node (ref "D6") (pin "1") (pinfunction "1_1") (pintype "passive"))
      (node (ref "D8") (pin "1") (pinfunction "1_1") (pintype "passive"))
      (node (ref "D9") (pin "1") (pinfunction "1_1") (pintype "passive"))
      (node (ref "EPD_C1") (pin "1") (pinfunction "1_1") (pintype "passive"))
      (node (ref "EPD_C10") (pin "1") (pinfunction "1_1") (pintype "passive"))
      (node (ref "EPD_C11") (pin "1") (pinfunction "1_1") (pintype "passive"))
      (node (ref "EPD_C12") (pin "1") (pinfunction "1_1") (pintype "passive"))
      (node (ref "EPD_C2") (pin "1") (pinfunction "1_1") (pintype "passive"))
      (node (ref "EPD_C5") (pin "1") (pinfunction "1_1") (pintype "passive"))
      (node (ref "EPD_C6") (pin "1") (pinfunction "1_1") (pintype "passive"))
      (node (ref "EPD_C7") (pin "1") (pinfunction "1_1") (pintype "passive"))
      (node (ref "EPD_C8") (pin "1") (pinfunction "1_1") (pintype "passive"))
      (node (ref "EPD_C9") (pin "1") (pinfunction "1_1") (pintype "passive"))
      (node (ref "IC1") (pin "3") (pinfunction "GND_3") (pintype "bidirectional"))
      (node (ref "IC4") (pin "2") (pinfunction "VSS_2") (pintype "bidirectional"))
      (node (ref "J1") (pin "17") (pinfunction "17_17") (pintype "bidirectional"))
      (node (ref "J1") (pin "8") (pinfunction "8_8") (pintype "bidirectional"))
      (node (ref "J1") (pin "MP1") (pinfunction "MP1_MP1") (pintype "bidirectional"))
      (node (ref "J1") (pin "MP2") (pinfunction "MP2_MP2") (pintype "bidirectional"))
      (node (ref "J2") (pin "A1") (pinfunction "A1_A1") (pintype "bidirectional"))
      (node (ref "J2") (pin "A12") (pinfunction "A12_A12") (pintype "bidirectional"))
      (node (ref "J2") (pin "B1") (pinfunction "B1_B1") (pintype "bidirectional"))
      (node (ref "J2") (pin "B12") (pinfunction "B12_B12") (pintype "bidirectional"))
      (node (ref "J2") (pin "MP1") (pinfunction "MP1_MP1") (pintype "bidirectional"))
      (node (ref "J2") (pin "MP2") (pinfunction "MP2_MP2") (pintype "bidirectional"))
      (node (ref "J2") (pin "MP3") (pinfunction "MP3_MP3") (pintype "bidirectional"))
      (node (ref "J2") (pin "MP4") (pinfunction "MP4_MP4") (pintype "bidirectional"))
      (node (ref "J3") (pin "1") (pinfunction "1_1") (pintype "power_in"))
      (node (ref "J4") (pin "G1") (pinfunction "GND_1_G1") (pintype "bidirectional"))
      (node (ref "J4") (pin "G2") (pinfunction "GND_2_G2") (pintype "bidirectional"))
      (node (ref "J4") (pin "G3") (pinfunction "GND_3_G3") (pintype "bidirectional"))
      (node (ref "J4") (pin "G4") (pinfunction "GND_4_G4") (pintype "bidirectional"))
      (node (ref "J4") (pin "P6") (pinfunction "VSS_P6") (pintype "bidirectional"))
      (node (ref "R1_PWRUSB") (pin "1") (pinfunction "1_1") (pintype "passive"))
      (node (ref "R2") (pin "1") (pinfunction "1_1") (pintype "passive"))
      (node (ref "R2-USB") (pin "2") (pinfunction "2_2") (pintype "passive"))
      (node (ref "R2-USB1") (pin "1") (pinfunction "1_1") (pintype "passive"))
      (node (ref "R2_BAT") (pin "1") (pinfunction "1_1") (pintype "passive"))
      (node (ref "R4") (pin "1") (pinfunction "1_1") (pintype "passive"))
      (node (ref "RESET_BUTTON") (pin "1") (pinfunction "1_1") (pintype "passive"))
      (node (ref "RESET_BUTTON") (pin "2") (pinfunction "2_2") (pintype "passive"))
      (node (ref "SENSOR2") (pin "1") (pinfunction "GND_1") (pintype "power_in"))
      (node (ref "SENSOR2") (pin "5") (pinfunction "SDO_5") (pintype "bidirectional"))
      (node (ref "SENSOR2") (pin "7") (pinfunction "GND_7") (pintype "power_in"))
      (node (ref "SJ1") (pin "1") (pinfunction "1_1") (pintype "passive"))
      (node (ref "TP4") (pin "TP") (pinfunction "TP_TP") (pintype "input"))
      (node (ref "TP5") (pin "TP") (pinfunction "TP_TP") (pintype "input"))
      (node (ref "U1") (pin "4") (pinfunction "GND_4") (pintype "power_in"))
      (node (ref "U1") (pin "9") (pinfunction "EXP_9") (pintype "passive"))
      (node (ref "U2") (pin "1") (pinfunction "GND_1") (pintype "power_in"))
      (node (ref "U2") (pin "28") (pinfunction "GND_28") (pintype "power_in"))
      (node (ref "U2") (pin "29_1") (pinfunction "GND_29_1") (pintype "power_in"))
      (node (ref "U2") (pin "29_2") (pinfunction "GND_29_2") (pintype "power_in"))
      (node (ref "U2") (pin "29_3") (pinfunction "GND_29_3") (pintype "power_in"))
      (node (ref "U2") (pin "29_4") (pinfunction "GND_29_4") (pintype "power_in"))
      (node (ref "U2") (pin "29_5") (pinfunction "GND_29_5") (pintype "power_in"))
      (node (ref "U2") (pin "29_6") (pinfunction "GND_29_6") (pintype "power_in"))
      (node (ref "U2") (pin "29_7") (pinfunction "GND_29_7") (pintype "power_in"))
      (node (ref "U2") (pin "29_8") (pinfunction "GND_29_8") (pintype "power_in"))
      (node (ref "U2") (pin "29_9") (pinfunction "GND_29_9") (pintype "power_in"))
      (node (ref "U3") (pin "13") (pinfunction "GND_13") (pintype "power_in"))
      (node (ref "U4") (pin "1") (pinfunction "CTG_1") (pintype "power_in"))
      (node (ref "U4") (pin "4") (pinfunction "GND_4") (pintype "power_in"))
      (node (ref "U4") (pin "6") (pinfunction "QSTRT_6") (pintype "input"))
      (node (ref "U4") (pin "9") (pinfunction "EP_9") (pintype "power_in"))
      (node (ref "U5") (pin "2") (pinfunction "VSS_2") (pintype "power_in"))
    )
    (net (code "14") (name "GPIO8") (class "Default")
      (node (ref "R1") (pin "1") (pinfunction "1_1") (pintype "passive"))
      (node (ref "U2") (pin "10") (pinfunction "IO8_10") (pintype "bidirectional"))
    )
    (net (code "15") (name "I2C_PW") (class "Default")
      (node (ref "C1") (pin "1") (pinfunction "1_1") (pintype "passive"))
      (node (ref "C2") (pin "1") (pinfunction "1_1") (pintype "passive"))
      (node (ref "R1-PINH") (pin "2") (pinfunction "2_2") (pintype "passive"))
      (node (ref "R2-PINH") (pin "2") (pinfunction "2_2") (pintype "passive"))
      (node (ref "SENSOR2") (pin "2") (pinfunction "CSB_2") (pintype "input"))
      (node (ref "SENSOR2") (pin "6") (pinfunction "VDDIO_6") (pintype "power_in"))
      (node (ref "SENSOR2") (pin "8") (pinfunction "VDD_8") (pintype "power_in"))
      (node (ref "U2") (pin "17") (pinfunction "IO19_17") (pintype "bidirectional"))
    )
    (net (code "16") (name "INT_RTC") (class "Default")
      (node (ref "R1_PINH1") (pin "1") (pinfunction "1_1") (pintype "passive"))
      (node (ref "TP17") (pin "TP") (pinfunction "TP_TP") (pintype "input"))
      (node (ref "U2") (pin "8") (pinfunction "IO0_8") (pintype "bidirectional"))
      (node (ref "U3") (pin "3") (pinfunction "SQW/~{INT}_3") (pintype "output"))
    )
    (net (code "17") (name "IO{slash}BOOT") (class "Default")
      (node (ref "BOOT_BUTTON") (pin "3") (pinfunction "3_3") (pintype "passive"))
      (node (ref "BOOT_BUTTON") (pin "4") (pinfunction "4_4") (pintype "passive"))
      (node (ref "C6") (pin "1") (pinfunction "1_1") (pintype "passive"))
      (node (ref "R_BOOT") (pin "1") (pinfunction "1_1") (pintype "passive"))
      (node (ref "U2") (pin "15") (pinfunction "IO9_15") (pintype "bidirectional"))
    )
    (net (code "18") (name "IO{slash}CHANGE") (class "Default")
      (node (ref "C10") (pin "1") (pinfunction "1_1") (pintype "passive"))
      (node (ref "CHANGE_BUTTON") (pin "3") (pinfunction "3_3") (pintype "passive"))
      (node (ref "CHANGE_BUTTON") (pin "4") (pinfunction "4_4") (pintype "passive"))
      (node (ref "R_CHANGE") (pin "1") (pinfunction "1_1") (pintype "passive"))
      (node (ref "U2") (pin "23") (pinfunction "IO15_23") (pintype "bidirectional"))
    )
    (net (code "19") (name "MISO") (class "Default")
      (node (ref "D12") (pin "2") (pinfunction "2_2") (pintype "passive"))
      (node (ref "J4") (pin "P7") (pinfunction "DAT0_P7") (pintype "bidirectional"))
      (node (ref "R8") (pin "1") (pinfunction "1_1") (pintype "passive"))
      (node (ref "TP8") (pin "TP") (pinfunction "TP_TP") (pintype "input"))
      (node (ref "U1") (pin "2") (pinfunction "DO(IO1)_2") (pintype "bidirectional"))
      (node (ref "U2") (pin "27") (pinfunction "IO2_27") (pintype "bidirectional"))
    )
    (net (code "20") (name "MOSI") (class "Default")
      (node (ref "D11") (pin "2") (pinfunction "2_2") (pintype "passive"))
      (node (ref "J1") (pin "14") (pinfunction "14_14") (pintype "bidirectional"))
      (node (ref "J4") (pin "P3") (pinfunction "CMD_P3") (pintype "bidirectional"))
      (node (ref "R7") (pin "1") (pinfunction "1_1") (pintype "passive"))
      (node (ref "TP9") (pin "TP") (pinfunction "TP_TP") (pintype "input"))
      (node (ref "U1") (pin "5") (pinfunction "DI(IO0)_5") (pintype "bidirectional"))
      (node (ref "U2") (pin "7") (pinfunction "IO7_7") (pintype "bidirectional"))
    )
    (net (code "21") (name "Net-(CHG_LED-PadC)") (class "Default")
      (node (ref "CHG_LED") (pin "C") (pinfunction "C_C") (pintype "passive"))
      (node (ref "R1_BAT") (pin "1") (pinfunction "1_1") (pintype "passive"))
    )
    (net (code "22") (name "Net-(D2-CATHODE)") (class "Default")
      (node (ref "C1_BAT1") (pin "1") (pinfunction "1_1") (pintype "passive"))
      (node (ref "D2") (pin "1") (pinfunction "CATHODE_1") (pintype "bidirectional"))
      (node (ref "IC4") (pin "1") (pinfunction "VIN_1") (pintype "bidirectional"))
      (node (ref "IC4") (pin "3") (pinfunction "CE_3") (pintype "bidirectional"))
      (node (ref "Q1") (pin "2") (pinfunction "S_2") (pintype "bidirectional"))
    )
    (net (code "23") (name "Net-(D3-A)") (class "Default")
      (node (ref "C4") (pin "1") (pinfunction "1_1") (pintype "passive"))
      (node (ref "D3") (pin "2") (pinfunction "A_2") (pintype "bidirectional"))
      (node (ref "D4") (pin "1") (pinfunction "K_1") (pintype "bidirectional"))
    )
    (net (code "24") (name "Net-(D7-CATHODE)") (class "Default")
      (node (ref "D7") (pin "1") (pinfunction "CATHODE_1") (pintype "bidirectional"))
      (node (ref "R_CAPACITOR") (pin "1") (pinfunction "1_1") (pintype "passive"))
    )
    (net (code "25") (name "Net-(EPD_C1-Pad2)") (class "Default")
      (node (ref "EPD_C1") (pin "2") (pinfunction "2_2") (pintype "passive"))
      (node (ref "J1") (pin "4") (pinfunction "4_4") (pintype "bidirectional"))
    )
    (net (code "26") (name "Net-(EPD_C2-Pad2)") (class "Default")
      (node (ref "EPD_C2") (pin "2") (pinfunction "2_2") (pintype "passive"))
      (node (ref "J1") (pin "5") (pinfunction "5_5") (pintype "bidirectional"))
    )
    (net (code "27") (name "Net-(EPD_C6-Pad2)") (class "Default")
      (node (ref "EPD_C6") (pin "2") (pinfunction "2_2") (pintype "passive"))
      (node (ref "J1") (pin "18") (pinfunction "18_18") (pintype "bidirectional"))
    )
    (net (code "28") (name "Net-(EPD_C7-Pad2)") (class "Default")
      (node (ref "EPD_C7") (pin "2") (pinfunction "2_2") (pintype "passive"))
      (node (ref "J1") (pin "19") (pinfunction "19_19") (pintype "bidirectional"))
    )
    (net (code "29") (name "Net-(EPD_C8-Pad2)") (class "Default")
      (node (ref "EPD_C8") (pin "2") (pinfunction "2_2") (pintype "passive"))
      (node (ref "J1") (pin "20") (pinfunction "20_20") (pintype "bidirectional"))
    )
    (net (code "30") (name "Net-(EPD_C10-Pad2)") (class "Default")
      (node (ref "EPD_C10") (pin "2") (pinfunction "2_2") (pintype "passive"))
      (node (ref "J1") (pin "22") (pinfunction "22_22") (pintype "bidirectional"))
    )
    (net (code "31") (name "Net-(EPD_C12-Pad2)") (class "Default")
      (node (ref "EPD_C12") (pin "2") (pinfunction "2_2") (pintype "passive"))
      (node (ref "J1") (pin "24") (pinfunction "24_24") (pintype "bidirectional"))
    )
    (net (code "32") (name "Net-(IC1-CT)") (class "Default")
      (node (ref "C_DELAY") (pin "1") (pinfunction "1_1") (pintype "passive"))
      (node (ref "IC1") (pin "5") (pinfunction "CT_5") (pintype "bidirectional"))
    )
    (net (code "33") (name "Net-(J2-PadA5)") (class "Default")
      (node (ref "J2") (pin "A5") (pinfunction "A5_A5") (pintype "bidirectional"))
      (node (ref "R2-USB1") (pin "2") (pinfunction "2_2") (pintype "passive"))
    )
    (net (code "34") (name "Net-(J2-PadB5)") (class "Default")
      (node (ref "J2") (pin "B5") (pinfunction "B5_B5") (pintype "bidirectional"))
      (node (ref "R2-USB") (pin "1") (pinfunction "1_1") (pintype "passive"))
    )
    (net (code "35") (name "Net-(U5-PROG)") (class "Default")
      (node (ref "R2_BAT") (pin "2") (pinfunction "2_2") (pintype "passive"))
      (node (ref "U5") (pin "5") (pinfunction "PROG_5") (pintype "input"))
    )
    (net (code "36") (name "Net-(U5-STAT)") (class "Default")
      (node (ref "R1_BAT") (pin "2") (pinfunction "2_2") (pintype "passive"))
      (node (ref "U5") (pin "1") (pinfunction "STAT_1") (pintype "output"))
    )
    (net (code "37") (name "PREVGH") (class "Default")
      (node (ref "D5") (pin "1") (pinfunction "K_1") (pintype "bidirectional"))
      (node (ref "EPD_C9") (pin "2") (pinfunction "2_2") (pintype "passive"))
      (node (ref "J1") (pin "21") (pinfunction "21_21") (pintype "bidirectional"))
    )
    (net (code "38") (name "PREVGL") (class "Default")
      (node (ref "D4") (pin "2") (pinfunction "A_2") (pintype "bidirectional"))
      (node (ref "EPD_C11") (pin "2") (pinfunction "2_2") (pintype "passive"))
      (node (ref "J1") (pin "23") (pinfunction "23_23") (pintype "bidirectional"))
    )
    (net (code "39") (name "RESE") (class "Default")
      (node (ref "J1") (pin "3") (pinfunction "3_3") (pintype "bidirectional"))
      (node (ref "Q3") (pin "2") (pinfunction "S_2") (pintype "bidirectional"))
      (node (ref "R3") (pin "2") (pinfunction "2_2") (pintype "passive"))
    )
    (net (code "40") (name "RESE'") (class "Default")
      (node (ref "R2") (pin "2") (pinfunction "2_2") (pintype "passive"))
      (node (ref "R3") (pin "1") (pinfunction "1_1") (pintype "passive"))
      (node (ref "SJ1") (pin "2") (pinfunction "2_2") (pintype "passive"))
    )
    (net (code "41") (name "RESET") (class "Default")
      (node (ref "C5") (pin "1") (pinfunction "1_1") (pintype "passive"))
      (node (ref "IC1") (pin "1") (pinfunction "VOUT_1") (pintype "bidirectional"))
      (node (ref "RESET_BUTTON") (pin "3") (pinfunction "3_3") (pintype "passive"))
      (node (ref "RESET_BUTTON") (pin "4") (pinfunction "4_4") (pintype "passive"))
      (node (ref "R_RESET") (pin "1") (pinfunction "1_1") (pintype "passive"))
      (node (ref "U2") (pin "3") (pinfunction "EN_3") (pintype "input"))
    )
    (net (code "42") (name "RTC_RST") (class "Default")
      (node (ref "U2") (pin "16") (pinfunction "IO18_16") (pintype "bidirectional"))
      (node (ref "U3") (pin "4") (pinfunction "~{RST}_4") (pintype "input"))
    )
    (net (code "43") (name "RX") (class "Default")
      (node (ref "TP2") (pin "TP") (pinfunction "TP_TP") (pintype "input"))
      (node (ref "U2") (pin "24") (pinfunction "RXD0/GPIO17_24") (pintype "bidirectional"))
    )
    (net (code "44") (name "SCK") (class "Default")
      (node (ref "D10") (pin "2") (pinfunction "2_2") (pintype "passive"))
      (node (ref "J1") (pin "13") (pinfunction "13_13") (pintype "bidirectional"))
      (node (ref "J4") (pin "P5") (pinfunction "CLK_P5") (pintype "bidirectional"))
      (node (ref "R6") (pin "1") (pinfunction "1_1") (pintype "passive"))
      (node (ref "TP10") (pin "TP") (pinfunction "TP_TP") (pintype "input"))
      (node (ref "U1") (pin "6") (pinfunction "CLK_6") (pintype "input"))
      (node (ref "U2") (pin "6") (pinfunction "IO6_6") (pintype "bidirectional"))
    )
    (net (code "45") (name "SCL") (class "Default")
      (node (ref "J3") (pin "4") (pinfunction "4_4") (pintype "passive"))
      (node (ref "R2-PINH") (pin "1") (pinfunction "1_1") (pintype "passive"))
      (node (ref "SENSOR2") (pin "4") (pinfunction "SCK_4") (pintype "input"))
      (node (ref "U2") (pin "20") (pinfunction "IO22_20") (pintype "bidirectional"))
      (node (ref "U3") (pin "16") (pinfunction "SCL_16") (pintype "input"))
      (node (ref "U4") (pin "7") (pinfunction "SCL_7") (pintype "input"))
    )
    (net (code "46") (name "SDA") (class "Default")
      (node (ref "J3") (pin "3") (pinfunction "3_3") (pintype "passive"))
      (node (ref "R1-PINH") (pin "1") (pinfunction "1_1") (pintype "passive"))
      (node (ref "SENSOR2") (pin "3") (pinfunction "SDI_3") (pintype "bidirectional"))
      (node (ref "U2") (pin "19") (pinfunction "IO21_19") (pintype "bidirectional"))
      (node (ref "U3") (pin "15") (pinfunction "SDA_15") (pintype "bidirectional"))
      (node (ref "U4") (pin "8") (pinfunction "SDA_8") (pintype "bidirectional"))
    )
    (net (code "47") (name "SRC") (class "Default")
      (node (ref "C4") (pin "2") (pinfunction "2_2") (pintype "passive"))
      (node (ref "D5") (pin "2") (pinfunction "A_2") (pintype "bidirectional"))
      (node (ref "L1") (pin "1") (pinfunction "1_1") (pintype "passive"))
      (node (ref "Q3") (pin "3") (pinfunction "D_3") (pintype "bidirectional"))
    )
    (net (code "48") (name "SS_SD") (class "Default")
      (node (ref "D8") (pin "2") (pinfunction "2_2") (pintype "passive"))
      (node (ref "J4") (pin "P2") (pinfunction "CD/DAT3_P2") (pintype "bidirectional"))
      (node (ref "R10") (pin "1") (pinfunction "1_1") (pintype "passive"))
      (node (ref "U2") (pin "4") (pinfunction "IO4_4") (pintype "bidirectional"))
    )
    (net (code "49") (name "TX") (class "Default")
      (node (ref "TP1") (pin "TP") (pinfunction "TP_TP") (pintype "input"))
      (node (ref "U2") (pin "25") (pinfunction "TXD0/GPIO16_25") (pintype "bidirectional"))
    )
    (net (code "50") (name "USB_D+") (class "Default")
      (node (ref "D1") (pin "1") (pinfunction "I/O1_1_1") (pintype "bidirectional"))
      (node (ref "U2") (pin "14") (pinfunction "IO13_14") (pintype "bidirectional"))
    )
    (net (code "51") (name "USB_D-") (class "Default")
      (node (ref "D1") (pin "3") (pinfunction "I/O2_1_3") (pintype "bidirectional"))
      (node (ref "U2") (pin "13") (pinfunction "IO12_13") (pintype "bidirectional"))
    )
    (net (code "52") (name "VBAT") (class "Default")
      (node (ref "C2_BAT") (pin "1") (pinfunction "1_1") (pintype "passive"))
      (node (ref "Q1") (pin "3") (pinfunction "D_3") (pintype "bidirectional"))
      (node (ref "TP3") (pin "TP") (pinfunction "TP_TP") (pintype "input"))
      (node (ref "U4") (pin "2") (pinfunction "CELL_2") (pintype "power_in"))
      (node (ref "U4") (pin "3") (pinfunction "VDD_3") (pintype "power_in"))
      (node (ref "U5") (pin "3") (pinfunction "VBAT_3") (pintype "power_in"))
    )
    (net (code "53") (name "VBUS") (class "Default")
      (node (ref "C1_BAT") (pin "1") (pinfunction "1_1") (pintype "passive"))
      (node (ref "C4_USB") (pin "1") (pinfunction "1_1") (pintype "passive"))
      (node (ref "C5_USB") (pin "1") (pinfunction "1_1") (pintype "passive"))
      (node (ref "CHG_LED") (pin "A") (pinfunction "A_A") (pintype "passive"))
      (node (ref "D1") (pin "5") (pinfunction "VBUS_5") (pintype "bidirectional"))
      (node (ref "D2") (pin "2") (pinfunction "ANODE_2") (pintype "bidirectional"))
      (node (ref "PFMF.050.1") (pin "2") (pinfunction "2_2") (pintype "passive"))
      (node (ref "Q1") (pin "1") (pinfunction "G_1") (pintype "bidirectional"))
      (node (ref "R1_PWRUSB") (pin "2") (pinfunction "2_2") (pintype "passive"))
      (node (ref "TP16") (pin "TP") (pinfunction "TP_TP") (pintype "input"))
      (node (ref "U5") (pin "4") (pinfunction "VIN_4") (pintype "power_in"))
    )
    (net (code "54") (name "VRTC") (class "Default")
      (node (ref "C10_SUPERCAP") (pin "2") (pinfunction "2_2") (pintype "passive"))
      (node (ref "C8") (pin "1") (pinfunction "1_1") (pintype "passive"))
      (node (ref "R_CAPACITOR") (pin "2") (pinfunction "2_2") (pintype "passive"))
      (node (ref "U3") (pin "14") (pinfunction "VBAT_14") (pintype "power_in"))
    )
    (net (code "55") (name "VUSB") (class "Default")
      (node (ref "J2") (pin "A4") (pinfunction "A4_A4") (pintype "bidirectional"))
      (node (ref "J2") (pin "A9") (pinfunction "A9_A9") (pintype "bidirectional"))
      (node (ref "J2") (pin "B4") (pinfunction "B4_B4") (pintype "bidirectional"))
      (node (ref "J2") (pin "B9") (pinfunction "B9_B9") (pintype "bidirectional"))
      (node (ref "PFMF.050.1") (pin "1") (pinfunction "1_1") (pintype "passive"))
    )
    (net (code "56") (name "unconnected-(IC1-NC-Pad4)") (class "Default")
      (node (ref "IC1") (pin "4") (pinfunction "NC_4") (pintype "no_connect"))
    )
    (net (code "57") (name "unconnected-(IC4-NC-Pad4)") (class "Default")
      (node (ref "IC4") (pin "4") (pinfunction "NC_4") (pintype "no_connect"))
    )
    (net (code "58") (name "unconnected-(J1-Pad1)") (class "Default")
      (node (ref "J1") (pin "1") (pinfunction "1_1") (pintype "bidirectional"))
    )
    (net (code "59") (name "unconnected-(J1-Pad6)") (class "Default")
      (node (ref "J1") (pin "6") (pinfunction "6_6") (pintype "bidirectional"))
    )
    (net (code "60") (name "unconnected-(J1-Pad7)") (class "Default")
      (node (ref "J1") (pin "7") (pinfunction "7_7") (pintype "bidirectional"))
    )
    (net (code "61") (name "unconnected-(J2-PadA8)") (class "Default")
      (node (ref "J2") (pin "A8") (pinfunction "A8_A8") (pintype "bidirectional"))
    )
    (net (code "62") (name "unconnected-(J2-PadB8)") (class "Default")
      (node (ref "J2") (pin "B8") (pinfunction "B8_B8") (pintype "bidirectional"))
    )
    (net (code "63") (name "unconnected-(J4-DAT1-PadP8)") (class "Default")
      (node (ref "J4") (pin "P8") (pinfunction "DAT1_P8") (pintype "bidirectional"))
    )
    (net (code "64") (name "unconnected-(J4-DAT2-PadP1)") (class "Default")
      (node (ref "J4") (pin "P1") (pinfunction "DAT2_P1") (pintype "bidirectional"))
    )
    (net (code "65") (name "unconnected-(J4-DETECTION_1-PadS1)") (class "Default")
      (node (ref "J4") (pin "S1") (pinfunction "DETECTION_1_S1") (pintype "bidirectional"))
    )
    (net (code "66") (name "unconnected-(J4-DETECTION_2-PadS2)") (class "Default")
      (node (ref "J4") (pin "S2") (pinfunction "DETECTION_2_S2") (pintype "bidirectional"))
    )
    (net (code "67") (name "unconnected-(U2-NC-Pad22)") (class "Default")
      (node (ref "U2") (pin "22") (pinfunction "NC_22") (pintype "no_connect"))
    )
    (net (code "68") (name "unconnected-(U4-~{ALERT}-Pad5)") (class "Default")
      (node (ref "U4") (pin "5") (pinfunction "~{ALERT}_5") (pintype "output"))
    )
  )
)
